# 05_Communication.net
KiCad netlist of a schematic drawn in Altium Designer
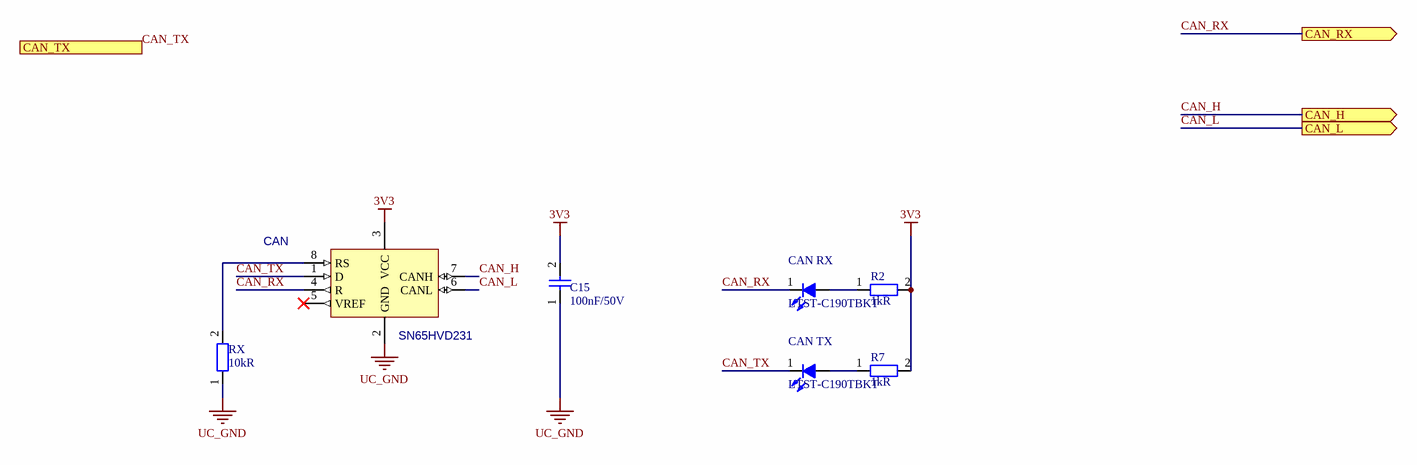
[diagram p0: 05_Communication.SchDoc]

(export (version "E")
  (design (tool "Eeschema 10.0.6"))
  (components
    (comp (ref "C15")
      (value "100nF/50V")
      (footprint "CAPC1005X05L")
      (description "Cap MLCC, 100nF, 50V, X7R, 10%, 0402")
      (fields (field (name "TOLERANCE") "10%"))
      (libsource (lib "Altium Concord Pro on Altium 365") (part "CAP-NP-2"))
    )
    (comp (ref "CAN")
      (value "SN65HVD231")
      (footprint "SOIC127P600X175-8L")
      (description "Bus Interface, CAN Transceiver, 3..3.6V, 1 Ch, SOIC-8, L5B3.98H1.75")
      (libsource (lib "Altium Concord Pro on Altium 365") (part "SN65HVD231-Symbol-1"))
    )
    (comp (ref "CAN RX")
      (value "LTST-C190TBKT")
      (footprint "LEDSC160X80X80-2Lbl")
      (description "LED, Blue, 20mA, 2.8V, 0603")
      (libsource (lib "Altium Concord Pro on Altium 365") (part "LED-BLUE-AK-2"))
    )
    (comp (ref "CAN TX")
      (value "LTST-C190TBKT")
      (footprint "LEDSC160X80X80-2Lbl")
      (description "LED, Blue, 20mA, 2.8V, 0603")
      (libsource (lib "Altium Concord Pro on Altium 365") (part "LED-BLUE-AK-2"))
    )
    (comp (ref "R2")
      (value "1kR")
      (footprint "RESC1005X04L")
      (description "Res, 1kR, 1%, 0.1W, 0402")
      (fields (field (name "POWER") "100mW") (field (name "TOLERANCE") "1%"))
      (libsource (lib "") (part "RES-2_1"))
    )
    (comp (ref "R7")
      (value "1kR")
      (footprint "RESC1005X04L")
      (description "Res, 1kR, 1%, 0.1W, 0402")
      (fields (field (name "POWER") "100mW") (field (name "TOLERANCE") "1%"))
      (libsource (lib "") (part "RES-2_1"))
    )
    (comp (ref "RX")
      (value "10kR")
      (footprint "RESC1005X04L")
      (description "Res, 10kR, 1%, 0.1W, 0402")
      (fields (field (name "POWER") "100mW") (field (name "TOLERANCE") "1%"))
      (libsource (lib "Altium Concord Pro on Altium 365") (part "RES-2"))
    )
  )
  (nets
    (net (code "1") (name "/CAN_H") (class "Default")
      (node (ref "CAN") (pin "7") (pinfunction "CANH_7") (pintype "bidirectional"))
    )
    (net (code "2") (name "/CAN_L") (class "Default")
      (node (ref "CAN") (pin "6") (pinfunction "CANL_6") (pintype "bidirectional"))
    )
    (net (code "3") (name "/CAN_RX") (class "Default")
      (node (ref "CAN") (pin "4") (pinfunction "R_4") (pintype "output"))
      (node (ref "CAN RX") (pin "1") (pinfunction "K_1") (pintype "passive"))
    )
    (net (code "4") (name "/CAN_TX") (class "Default")
      (node (ref "CAN") (pin "1") (pinfunction "D_1") (pintype "input"))
      (node (ref "CAN TX") (pin "1") (pinfunction "K_1") (pintype "passive"))
    )
    (net (code "5") (name "3V3") (class "Default")
      (node (ref "C15") (pin "2") (pinfunction "2_2") (pintype "passive"))
      (node (ref "CAN") (pin "3") (pinfunction "VCC_3") (pintype "power_in"))
      (node (ref "R2") (pin "2") (pinfunction "2_2") (pintype "passive"))
      (node (ref "R7") (pin "2") (pinfunction "2_2") (pintype "passive"))
    )
    (net (code "6") (name "Net-(CAN RX-A)") (class "Default")
      (node (ref "CAN RX") (pin "2") (pinfunction "A_2") (pintype "passive"))
      (node (ref "R2") (pin "1") (pinfunction "1_1") (pintype "passive"))
    )
    (net (code "7") (name "Net-(CAN TX-A)") (class "Default")
      (node (ref "CAN TX") (pin "2") (pinfunction "A_2") (pintype "passive"))
      (node (ref "R7") (pin "1") (pinfunction "1_1") (pintype "passive"))
    )
    (net (code "8") (name "Net-(CAN-RS)") (class "Default")
      (node (ref "CAN") (pin "8") (pinfunction "RS_8") (pintype "input"))
      (node (ref "RX") (pin "2") (pinfunction "2_2") (pintype "passive"))
    )
    (net (code "9") (name "UC_GND") (class "Default")
      (node (ref "C15") (pin "1") (pinfunction "1_1") (pintype "passive"))
      (node (ref "CAN") (pin "2") (pinfunction "GND_2") (pintype "power_in"))
      (node (ref "RX") (pin "1") (pinfunction "1_1") (pintype "passive"))
    )
    (net (code "10") (name "unconnected-(CAN-VREF-Pad5)") (class "Default")
      (node (ref "CAN") (pin "5") (pinfunction "VREF_5") (pintype "output+no_connect"))
    )
  )
)
